# IMX8_DISPLAY.net
KiCad netlist of a schematic drawn in Altium Designer
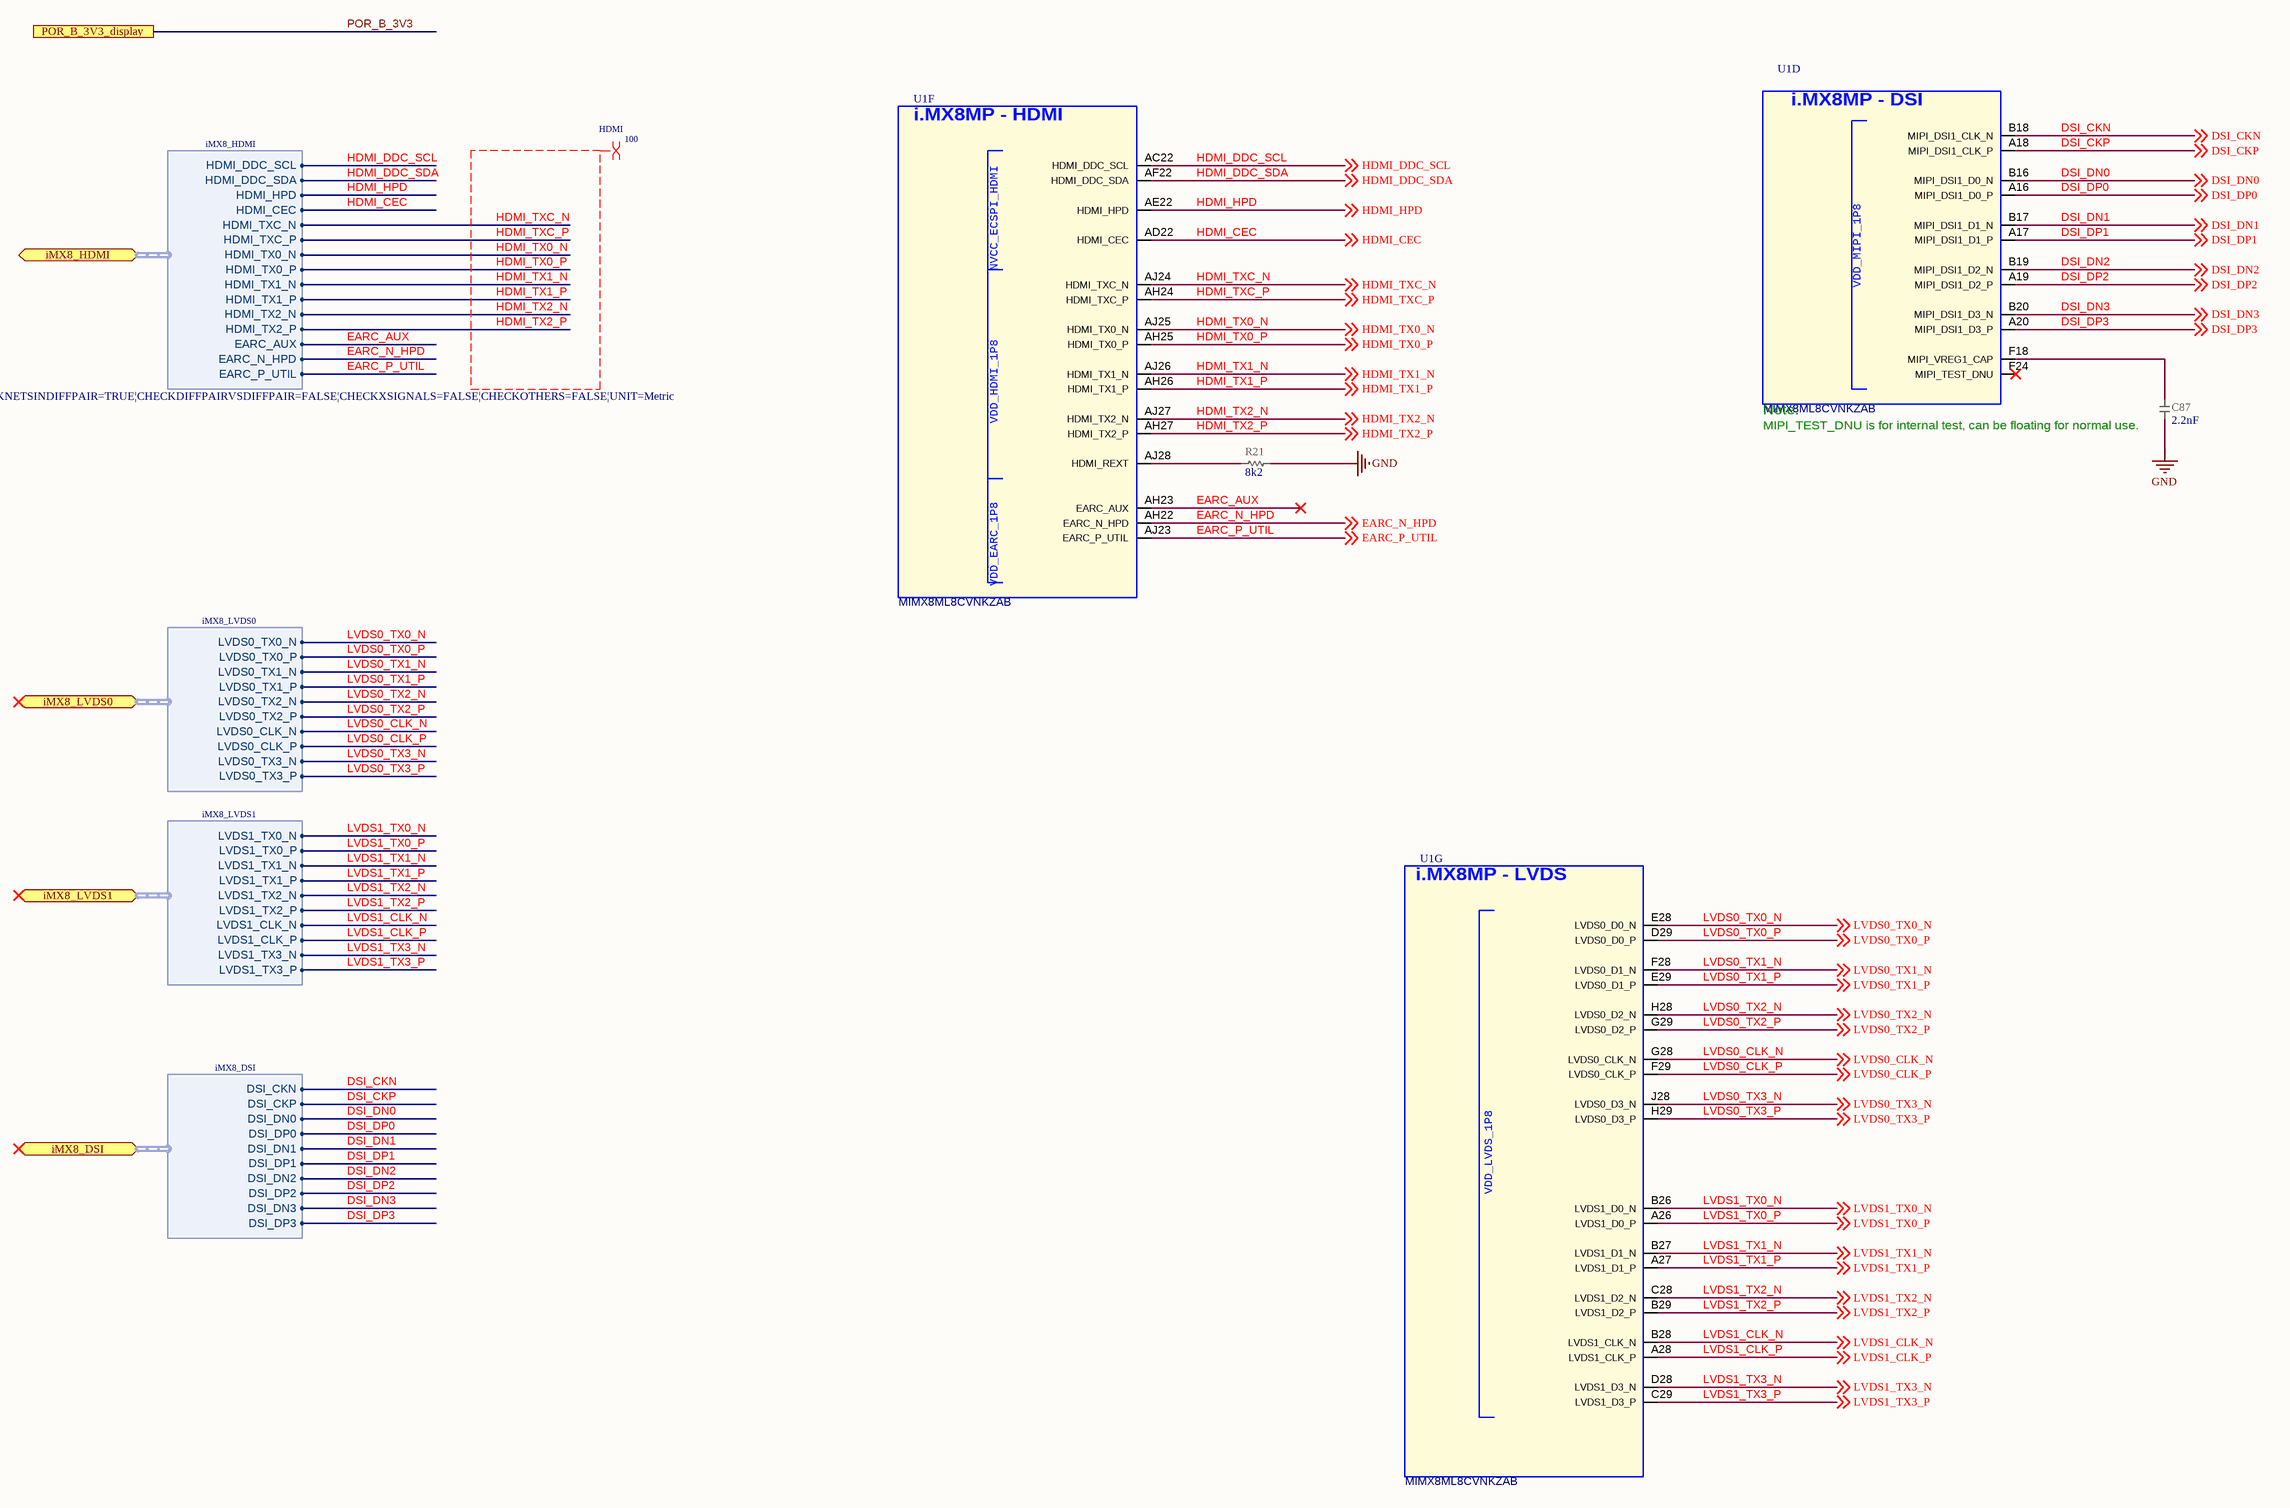
[diagram p0: IMX8_DISPLAY.SchDoc]

(export (version "E")
  (design (tool "Eeschema 10.0.6"))
  (components
    (comp (ref "C87")
      (value "2.2nF")
      (footprint "CAP_0201_UN1Q")
      (description "CAP")
      (fields (field (name "PART NUMBER") "GRM033R71E222KA12J") (field (name "MANUFACTURER") "Murata"))
      (libsource (lib "CM5_library") (part "CMP-001-000281-14"))
    )
    (comp (ref "R21")
      (value "8k2")
      (footprint "RES_0201_UN1Q")
      (description "RES")
      (fields (field (name "TOLERANCE") "1%") (field (name "PART NUMBER") "ERJ1GNF8201C"))
      (libsource (lib "robo_cam") (part "CMP-001-001255-9"))
    )
    (comp (ref "U1")
      (value "MIMX8ML8CVNKZAB")
      (footprint "BGA548C50P29X29_1500X1500X148")
      (description "CPU QUAD CORTEX A53+M4 1.6GHZ BGA548 Industrial")
      (fields
        (field (name "MANUFACTURER") "NXP Semiconductors")
        (field (name "PART NUMBER") "MIMX8ML8CVNKZAB")
        (field (name "SOURCE") "UUDET_KOMPONENTIT.SchLib")
      )
      (libsource (lib "robo_cam") (part "CMP-001-000983-8"))
    )
  )
  (nets
    (net (code "5") (name "/EARC_AUX") (class "Default")
      (node (ref "U1") (pin "AH23") (pinfunction "EARC_AUX_AH23") (pintype "passive"))
    )
    (net (code "11") (name "DSI_CKN") (class "Default")
      (node (ref "U1") (pin "B18") (pinfunction "MIPI_DSI1_CLK_N_B18") (pintype "passive"))
    )
    (net (code "12") (name "DSI_CKP") (class "Default")
      (node (ref "U1") (pin "A18") (pinfunction "MIPI_DSI1_CLK_P_A18") (pintype "passive"))
    )
    (net (code "13") (name "DSI_DN0") (class "Default")
      (node (ref "U1") (pin "B16") (pinfunction "MIPI_DSI1_D0_N_B16") (pintype "passive"))
    )
    (net (code "14") (name "DSI_DN1") (class "Default")
      (node (ref "U1") (pin "B17") (pinfunction "MIPI_DSI1_D1_N_B17") (pintype "passive"))
    )
    (net (code "15") (name "DSI_DN2") (class "Default")
      (node (ref "U1") (pin "B19") (pinfunction "MIPI_DSI1_D2_N_B19") (pintype "passive"))
    )
    (net (code "16") (name "DSI_DN3") (class "Default")
      (node (ref "U1") (pin "B20") (pinfunction "MIPI_DSI1_D3_N_B20") (pintype "passive"))
    )
    (net (code "17") (name "DSI_DP0") (class "Default")
      (node (ref "U1") (pin "A16") (pinfunction "MIPI_DSI1_D0_P_A16") (pintype "passive"))
    )
    (net (code "18") (name "DSI_DP1") (class "Default")
      (node (ref "U1") (pin "A17") (pinfunction "MIPI_DSI1_D1_P_A17") (pintype "passive"))
    )
    (net (code "19") (name "DSI_DP2") (class "Default")
      (node (ref "U1") (pin "A19") (pinfunction "MIPI_DSI1_D2_P_A19") (pintype "passive"))
    )
    (net (code "20") (name "DSI_DP3") (class "Default")
      (node (ref "U1") (pin "A20") (pinfunction "MIPI_DSI1_D3_P_A20") (pintype "passive"))
    )
    (net (code "21") (name "EARC_N_HPD") (class "Default")
      (node (ref "U1") (pin "AH22") (pinfunction "EARC_N_HPD_AH22") (pintype "passive"))
    )
    (net (code "22") (name "EARC_P_UTIL") (class "Default")
      (node (ref "U1") (pin "AJ23") (pinfunction "EARC_P_UTIL_AJ23") (pintype "passive"))
    )
    (net (code "23") (name "GND") (class "Default")
      (node (ref "C87") (pin "1") (pinfunction "1_1") (pintype "passive"))
      (node (ref "R21") (pin "2") (pinfunction "2_2") (pintype "passive"))
    )
    (net (code "24") (name "HDMI_CEC") (class "Default")
      (node (ref "U1") (pin "AD22") (pinfunction "HDMI_CEC_AD22") (pintype "passive"))
    )
    (net (code "25") (name "HDMI_DDC_SCL") (class "Default")
      (node (ref "U1") (pin "AC22") (pinfunction "HDMI_DDC_SCL_AC22") (pintype "passive"))
    )
    (net (code "26") (name "HDMI_DDC_SDA") (class "Default")
      (node (ref "U1") (pin "AF22") (pinfunction "HDMI_DDC_SDA_AF22") (pintype "passive"))
    )
    (net (code "27") (name "HDMI_HPD") (class "Default")
      (node (ref "U1") (pin "AE22") (pinfunction "HDMI_HPD_AE22") (pintype "passive"))
    )
    (net (code "28") (name "HDMI_TX0_N") (class "Default")
      (node (ref "U1") (pin "AJ25") (pinfunction "HDMI_TX0_N_AJ25") (pintype "passive"))
    )
    (net (code "29") (name "HDMI_TX0_P") (class "Default")
      (node (ref "U1") (pin "AH25") (pinfunction "HDMI_TX0_P_AH25") (pintype "passive"))
    )
    (net (code "30") (name "HDMI_TX1_N") (class "Default")
      (node (ref "U1") (pin "AJ26") (pinfunction "HDMI_TX1_N_AJ26") (pintype "passive"))
    )
    (net (code "31") (name "HDMI_TX1_P") (class "Default")
      (node (ref "U1") (pin "AH26") (pinfunction "HDMI_TX1_P_AH26") (pintype "passive"))
    )
    (net (code "32") (name "HDMI_TX2_N") (class "Default")
      (node (ref "U1") (pin "AJ27") (pinfunction "HDMI_TX2_N_AJ27") (pintype "passive"))
    )
    (net (code "33") (name "HDMI_TX2_P") (class "Default")
      (node (ref "U1") (pin "AH27") (pinfunction "HDMI_TX2_P_AH27") (pintype "passive"))
    )
    (net (code "34") (name "HDMI_TXC_N") (class "Default")
      (node (ref "U1") (pin "AJ24") (pinfunction "HDMI_TXC_N_AJ24") (pintype "passive"))
    )
    (net (code "35") (name "HDMI_TXC_P") (class "Default")
      (node (ref "U1") (pin "AH24") (pinfunction "HDMI_TXC_P_AH24") (pintype "passive"))
    )
    (net (code "36") (name "LVDS0_CLK_N") (class "Default")
      (node (ref "U1") (pin "G28") (pinfunction "LVDS0_CLK_N_G28") (pintype "passive"))
    )
    (net (code "37") (name "LVDS0_CLK_P") (class "Default")
      (node (ref "U1") (pin "F29") (pinfunction "LVDS0_CLK_P_F29") (pintype "passive"))
    )
    (net (code "38") (name "LVDS0_TX0_N") (class "Default")
      (node (ref "U1") (pin "E28") (pinfunction "LVDS0_D0_N_E28") (pintype "passive"))
    )
    (net (code "39") (name "LVDS0_TX0_P") (class "Default")
      (node (ref "U1") (pin "D29") (pinfunction "LVDS0_D0_P_D29") (pintype "passive"))
    )
    (net (code "40") (name "LVDS0_TX1_N") (class "Default")
      (node (ref "U1") (pin "F28") (pinfunction "LVDS0_D1_N_F28") (pintype "passive"))
    )
    (net (code "41") (name "LVDS0_TX1_P") (class "Default")
      (node (ref "U1") (pin "E29") (pinfunction "LVDS0_D1_P_E29") (pintype "passive"))
    )
    (net (code "42") (name "LVDS0_TX2_N") (class "Default")
      (node (ref "U1") (pin "H28") (pinfunction "LVDS0_D2_N_H28") (pintype "passive"))
    )
    (net (code "43") (name "LVDS0_TX2_P") (class "Default")
      (node (ref "U1") (pin "G29") (pinfunction "LVDS0_D2_P_G29") (pintype "passive"))
    )
    (net (code "44") (name "LVDS0_TX3_N") (class "Default")
      (node (ref "U1") (pin "J28") (pinfunction "LVDS0_D3_N_J28") (pintype "passive"))
    )
    (net (code "45") (name "LVDS0_TX3_P") (class "Default")
      (node (ref "U1") (pin "H29") (pinfunction "LVDS0_D3_P_H29") (pintype "passive"))
    )
    (net (code "46") (name "LVDS1_CLK_N") (class "Default")
      (node (ref "U1") (pin "B28") (pinfunction "LVDS1_CLK_N_B28") (pintype "passive"))
    )
    (net (code "47") (name "LVDS1_CLK_P") (class "Default")
      (node (ref "U1") (pin "A28") (pinfunction "LVDS1_CLK_P_A28") (pintype "passive"))
    )
    (net (code "48") (name "LVDS1_TX0_N") (class "Default")
      (node (ref "U1") (pin "B26") (pinfunction "LVDS1_D0_N_B26") (pintype "passive"))
    )
    (net (code "49") (name "LVDS1_TX0_P") (class "Default")
      (node (ref "U1") (pin "A26") (pinfunction "LVDS1_D0_P_A26") (pintype "passive"))
    )
    (net (code "50") (name "LVDS1_TX1_N") (class "Default")
      (node (ref "U1") (pin "B27") (pinfunction "LVDS1_D1_N_B27") (pintype "passive"))
    )
    (net (code "51") (name "LVDS1_TX1_P") (class "Default")
      (node (ref "U1") (pin "A27") (pinfunction "LVDS1_D1_P_A27") (pintype "passive"))
    )
    (net (code "52") (name "LVDS1_TX2_N") (class "Default")
      (node (ref "U1") (pin "C28") (pinfunction "LVDS1_D2_N_C28") (pintype "passive"))
    )
    (net (code "53") (name "LVDS1_TX2_P") (class "Default")
      (node (ref "U1") (pin "B29") (pinfunction "LVDS1_D2_P_B29") (pintype "passive"))
    )
    (net (code "54") (name "LVDS1_TX3_N") (class "Default")
      (node (ref "U1") (pin "D28") (pinfunction "LVDS1_D3_N_D28") (pintype "passive"))
    )
    (net (code "55") (name "LVDS1_TX3_P") (class "Default")
      (node (ref "U1") (pin "C29") (pinfunction "LVDS1_D3_P_C29") (pintype "passive"))
    )
    (net (code "56") (name "Net-(U1D-MIPI_VREG1_CAP)") (class "Default")
      (node (ref "C87") (pin "2") (pinfunction "2_2") (pintype "passive"))
      (node (ref "U1") (pin "F18") (pinfunction "MIPI_VREG1_CAP_F18") (pintype "passive"))
    )
    (net (code "57") (name "Net-(U1F-HDMI_REXT)") (class "Default")
      (node (ref "R21") (pin "1") (pinfunction "1_1") (pintype "passive"))
      (node (ref "U1") (pin "AJ28") (pinfunction "HDMI_REXT_AJ28") (pintype "passive"))
    )
    (net (code "58") (name "unconnected-(U1D-MIPI_TEST_DNU-PadF24)") (class "Default")
      (node (ref "U1") (pin "F24") (pinfunction "MIPI_TEST_DNU_F24") (pintype "passive+no_connect"))
    )
  )
)
